# 2LD-17-mk-1_2_0.net
KiCad netlist of a schematic drawn in EAGLE
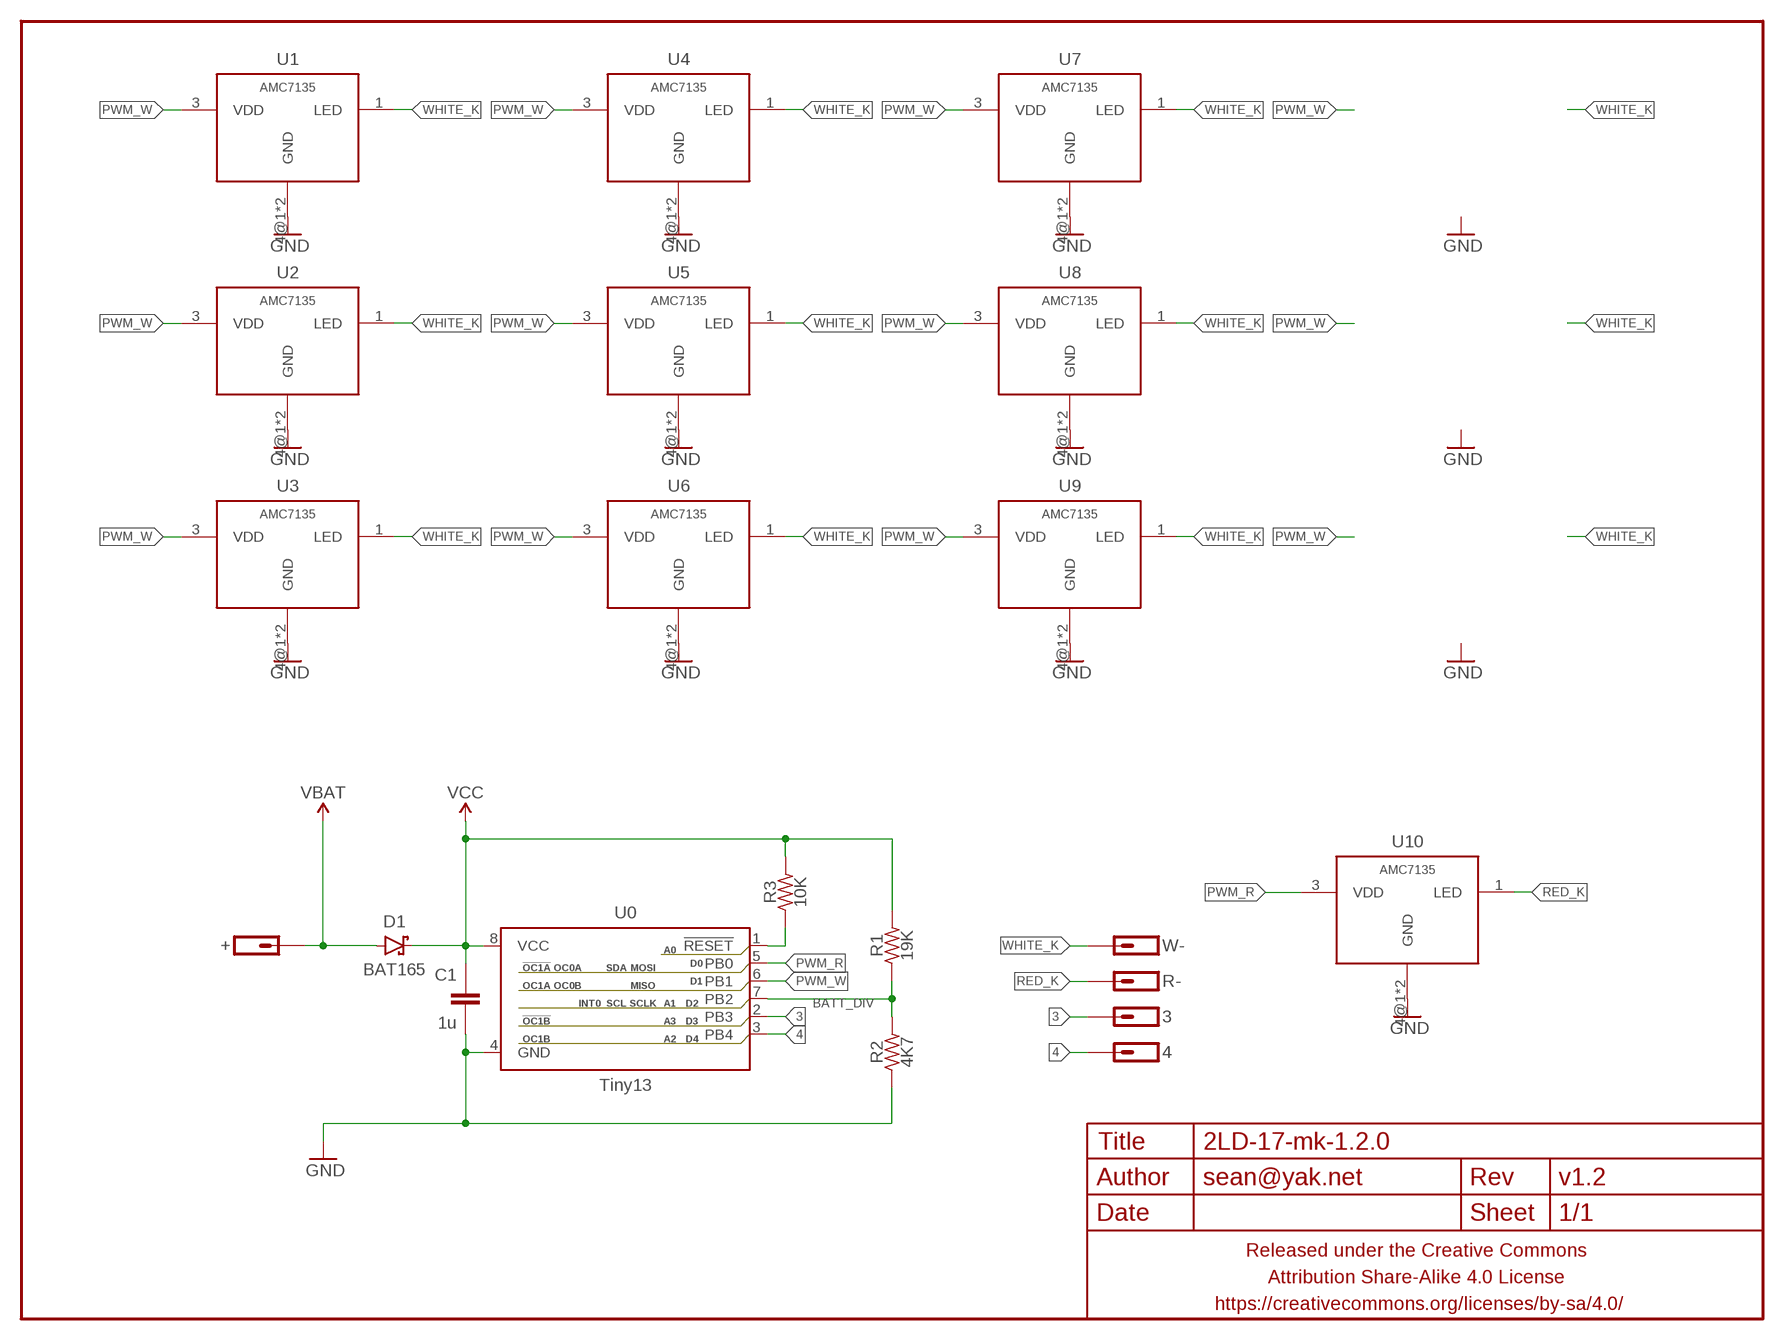
[diagram p0: schematic, sheet 1]

(export (version "E")
  (design (tool "Eeschema 10.0.6"))
  (components
    (comp (ref "+")
      (value "M01PTH-1.2MM-NS")
      (footprint "eagle-import:1X01-1.2MM-NS")
      (libsource (lib "eagle-import") (part "M01PTH-1.2MM-NS"))
    )
    (comp (ref "3")
      (value "M01SMD-1MM-DIA-NS")
      (footprint "eagle-import:1X01-SMD-1MM-DIA-NS")
      (libsource (lib "eagle-import") (part "M01SMD-1MM-DIA-NS"))
    )
    (comp (ref "4")
      (value "M01SMD-1MM-DIA-NS")
      (footprint "eagle-import:1X01-SMD-1MM-DIA-NS")
      (libsource (lib "eagle-import") (part "M01SMD-1MM-DIA-NS"))
    )
    (comp (ref "C1")
      (value "1u")
      (footprint "eagle-import:C0603-TIGHTER")
      (libsource (lib "eagle-import") (part "CAPACITOR-CERAMICC0603-TIGHTER"))
    )
    (comp (ref "D1")
      (value "BAT165")
      (footprint "eagle-import:SOD123-SCHOTTKY")
      (libsource (lib "eagle-import") (part "DIODE-SCHOTTKYSOD123"))
    )
    (comp (ref "FRAME1")
      (value "FRAME-LETTERNO_PACKAGE")
      (footprint "eagle-import:DUMMY")
      (fields (field (name "DESIGNER") "sean@yak.net") (field (name "VERSION") "v1.2"))
      (libsource (lib "eagle-import") (part "FRAME-LETTERNO_PACKAGE"))
    )
    (comp (ref "R-")
      (value "M01SMD-1.25MM-DIA")
      (footprint "eagle-import:1X01-SMD-1.25MM-DIA-NS")
      (libsource (lib "eagle-import") (part "M01SMD-1.25MM-DIA"))
    )
    (comp (ref "R1")
      (value "19K")
      (footprint "eagle-import:R0603-TIGHTER")
      (libsource (lib "eagle-import") (part "RESISTORR0603-TIGHTER"))
    )
    (comp (ref "R2")
      (value "4K7")
      (footprint "eagle-import:R0603-TIGHTER")
      (libsource (lib "eagle-import") (part "RESISTORR0603-TIGHTER"))
    )
    (comp (ref "R3")
      (value "10K")
      (footprint "eagle-import:R0603-TIGHTER")
      (libsource (lib "eagle-import") (part "RESISTORR0603-TIGHTER"))
    )
    (comp (ref "U0")
      (value "Tiny13")
      (footprint "eagle-import:SO08-NARROWER")
      (libsource (lib "eagle-import") (part "ATTINY13SOIC-NARROWPADS"))
    )
    (comp (ref "U1")
      (value "AMC7135")
      (footprint "eagle-import:SOT89-NOTHERM-ROUNDED")
      (libsource (lib "eagle-import") (part "AMC7135SOT-89-NOTHERM-ROUNDED"))
    )
    (comp (ref "U2")
      (value "AMC7135")
      (footprint "eagle-import:SOT89-NOTHERM-ROUNDED")
      (libsource (lib "eagle-import") (part "AMC7135SOT-89-NOTHERM-ROUNDED"))
    )
    (comp (ref "U3")
      (value "AMC7135")
      (footprint "eagle-import:SOT89-NOTHERM-ROUNDED")
      (libsource (lib "eagle-import") (part "AMC7135SOT-89-NOTHERM-ROUNDED"))
    )
    (comp (ref "U4")
      (value "AMC7135")
      (footprint "eagle-import:SOT89-NOTHERM-ROUNDED")
      (libsource (lib "eagle-import") (part "AMC7135SOT-89-NOTHERM-ROUNDED"))
    )
    (comp (ref "U5")
      (value "AMC7135")
      (footprint "eagle-import:SOT89-NOTHERM-ROUNDED")
      (libsource (lib "eagle-import") (part "AMC7135SOT-89-NOTHERM-ROUNDED"))
    )
    (comp (ref "U6")
      (value "AMC7135")
      (footprint "eagle-import:SOT89-NOTHERM-ROUNDED")
      (libsource (lib "eagle-import") (part "AMC7135SOT-89-NOTHERM-ROUNDED"))
    )
    (comp (ref "U7")
      (value "AMC7135")
      (footprint "eagle-import:SOT89-NOTHERM-ROUNDED")
      (libsource (lib "eagle-import") (part "AMC7135SOT-89-NOTHERM-ROUNDED"))
    )
    (comp (ref "U8")
      (value "AMC7135")
      (footprint "eagle-import:SOT89-NOTHERM-ROUNDED")
      (libsource (lib "eagle-import") (part "AMC7135SOT-89-NOTHERM-ROUNDED"))
    )
    (comp (ref "U9")
      (value "AMC7135")
      (footprint "eagle-import:SOT89-NOTHERM-ROUNDED")
      (libsource (lib "eagle-import") (part "AMC7135SOT-89-NOTHERM-ROUNDED"))
    )
    (comp (ref "U10")
      (value "AMC7135")
      (footprint "eagle-import:SOT89-NOTHERM-ROUNDED")
      (libsource (lib "eagle-import") (part "AMC7135SOT-89-NOTHERM-ROUNDED"))
    )
    (comp (ref "W-")
      (value "M01SMD-1.5MM-DIA-NS")
      (footprint "eagle-import:1X01-SMD-1.5MM-DIA-NS")
      (libsource (lib "eagle-import") (part "M01SMD-1.5MM-DIA-NS"))
    )
  )
  (nets
    (net (code "1") (name "/BATT_DIV") (class "Default")
      (node (ref "R1") (pin "1") (pinfunction "1_1") (pintype "passive"))
      (node (ref "R2") (pin "2") (pinfunction "2_2") (pintype "passive"))
      (node (ref "U0") (pin "7") (pinfunction "PB2_7") (pintype "bidirectional"))
    )
    (net (code "2") (name "3") (class "Default")
      (node (ref "3") (pin "P$1") (pinfunction "1_P$1") (pintype "passive"))
      (node (ref "U0") (pin "2") (pinfunction "PB3_2") (pintype "bidirectional"))
    )
    (net (code "3") (name "4") (class "Default")
      (node (ref "4") (pin "P$1") (pinfunction "1_P$1") (pintype "passive"))
      (node (ref "U0") (pin "3") (pinfunction "PB4_3") (pintype "bidirectional"))
    )
    (net (code "4") (name "GND") (class "Default")
      (node (ref "C1") (pin "2") (pinfunction "2_2") (pintype "passive"))
      (node (ref "R2") (pin "1") (pinfunction "1_1") (pintype "passive"))
      (node (ref "U0") (pin "4") (pinfunction "GND_4") (pintype "bidirectional"))
      (node (ref "U1") (pin "4@1") (pinfunction "GND_4@1") (pintype "bidirectional"))
      (node (ref "U1") (pin "4@2") (pinfunction "GND_4@2") (pintype "bidirectional"))
      (node (ref "U10") (pin "4@1") (pinfunction "GND_4@1") (pintype "bidirectional"))
      (node (ref "U10") (pin "4@2") (pinfunction "GND_4@2") (pintype "bidirectional"))
      (node (ref "U2") (pin "4@1") (pinfunction "GND_4@1") (pintype "bidirectional"))
      (node (ref "U2") (pin "4@2") (pinfunction "GND_4@2") (pintype "bidirectional"))
      (node (ref "U3") (pin "4@1") (pinfunction "GND_4@1") (pintype "bidirectional"))
      (node (ref "U3") (pin "4@2") (pinfunction "GND_4@2") (pintype "bidirectional"))
      (node (ref "U4") (pin "4@1") (pinfunction "GND_4@1") (pintype "bidirectional"))
      (node (ref "U4") (pin "4@2") (pinfunction "GND_4@2") (pintype "bidirectional"))
      (node (ref "U5") (pin "4@1") (pinfunction "GND_4@1") (pintype "bidirectional"))
      (node (ref "U5") (pin "4@2") (pinfunction "GND_4@2") (pintype "bidirectional"))
      (node (ref "U6") (pin "4@1") (pinfunction "GND_4@1") (pintype "bidirectional"))
      (node (ref "U6") (pin "4@2") (pinfunction "GND_4@2") (pintype "bidirectional"))
      (node (ref "U7") (pin "4@1") (pinfunction "GND_4@1") (pintype "bidirectional"))
      (node (ref "U7") (pin "4@2") (pinfunction "GND_4@2") (pintype "bidirectional"))
      (node (ref "U8") (pin "4@1") (pinfunction "GND_4@1") (pintype "bidirectional"))
      (node (ref "U8") (pin "4@2") (pinfunction "GND_4@2") (pintype "bidirectional"))
      (node (ref "U9") (pin "4@1") (pinfunction "GND_4@1") (pintype "bidirectional"))
      (node (ref "U9") (pin "4@2") (pinfunction "GND_4@2") (pintype "bidirectional"))
    )
    (net (code "5") (name "Net-(U0-~{RESET})") (class "Default")
      (node (ref "R3") (pin "1") (pinfunction "1_1") (pintype "passive"))
      (node (ref "U0") (pin "1") (pinfunction "~{RESET}_1") (pintype "bidirectional"))
    )
    (net (code "6") (name "PWM_R") (class "Default")
      (node (ref "U0") (pin "5") (pinfunction "PB0_5") (pintype "bidirectional"))
      (node (ref "U10") (pin "3") (pinfunction "VDD_3") (pintype "bidirectional"))
    )
    (net (code "7") (name "PWM_W") (class "Default")
      (node (ref "U0") (pin "6") (pinfunction "PB1_6") (pintype "bidirectional"))
      (node (ref "U1") (pin "3") (pinfunction "VDD_3") (pintype "bidirectional"))
      (node (ref "U2") (pin "3") (pinfunction "VDD_3") (pintype "bidirectional"))
      (node (ref "U3") (pin "3") (pinfunction "VDD_3") (pintype "bidirectional"))
      (node (ref "U4") (pin "3") (pinfunction "VDD_3") (pintype "bidirectional"))
      (node (ref "U5") (pin "3") (pinfunction "VDD_3") (pintype "bidirectional"))
      (node (ref "U6") (pin "3") (pinfunction "VDD_3") (pintype "bidirectional"))
      (node (ref "U7") (pin "3") (pinfunction "VDD_3") (pintype "bidirectional"))
      (node (ref "U8") (pin "3") (pinfunction "VDD_3") (pintype "bidirectional"))
      (node (ref "U9") (pin "3") (pinfunction "VDD_3") (pintype "bidirectional"))
    )
    (net (code "8") (name "RED_K") (class "Default")
      (node (ref "R-") (pin "P$1") (pinfunction "1_P$1") (pintype "passive"))
      (node (ref "U10") (pin "1") (pinfunction "LED_1") (pintype "bidirectional"))
    )
    (net (code "9") (name "VBAT") (class "Default")
      (node (ref "+") (pin "P$1") (pinfunction "1_P$1") (pintype "passive"))
      (node (ref "D1") (pin "A") (pinfunction "A_A") (pintype "passive"))
    )
    (net (code "10") (name "VCC") (class "Default")
      (node (ref "C1") (pin "1") (pinfunction "1_1") (pintype "passive"))
      (node (ref "D1") (pin "C") (pinfunction "C_C") (pintype "passive"))
      (node (ref "R1") (pin "2") (pinfunction "2_2") (pintype "passive"))
      (node (ref "R3") (pin "2") (pinfunction "2_2") (pintype "passive"))
      (node (ref "U0") (pin "8") (pinfunction "VCC_8") (pintype "bidirectional"))
    )
    (net (code "11") (name "WHITE_K") (class "Default")
      (node (ref "U1") (pin "1") (pinfunction "LED_1") (pintype "bidirectional"))
      (node (ref "U2") (pin "1") (pinfunction "LED_1") (pintype "bidirectional"))
      (node (ref "U3") (pin "1") (pinfunction "LED_1") (pintype "bidirectional"))
      (node (ref "U4") (pin "1") (pinfunction "LED_1") (pintype "bidirectional"))
      (node (ref "U5") (pin "1") (pinfunction "LED_1") (pintype "bidirectional"))
      (node (ref "U6") (pin "1") (pinfunction "LED_1") (pintype "bidirectional"))
      (node (ref "U7") (pin "1") (pinfunction "LED_1") (pintype "bidirectional"))
      (node (ref "U8") (pin "1") (pinfunction "LED_1") (pintype "bidirectional"))
      (node (ref "U9") (pin "1") (pinfunction "LED_1") (pintype "bidirectional"))
      (node (ref "W-") (pin "P$1") (pinfunction "1_P$1") (pintype "passive"))
    )
  )
)
